# FRAM.net
KiCad netlist of a schematic drawn in Altium Designer
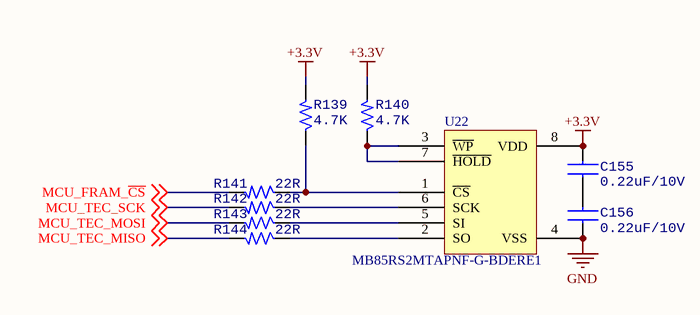
[diagram p0: FRAM.SchDoc]

(export (version "E")
  (design (tool "Eeschema 10.0.6"))
  (components
    (comp (ref "C155")
      (value "0.22uF/10V")
      (footprint "CAP-CER-0603")
      (libsource (lib "ID") (part "CAP-CER"))
    )
    (comp (ref "C156")
      (value "0.22uF/10V")
      (footprint "CAP-CER-0603")
      (libsource (lib "ID") (part "CAP-CER"))
    )
    (comp (ref "R139") (value "4.7K") (footprint "RES-SMD-0603") (libsource (lib "ID") (part "RES-SMD")))
    (comp (ref "R140") (value "4.7K") (footprint "RES-SMD-0603") (libsource (lib "ID") (part "RES-SMD")))
    (comp (ref "R141") (value "22R") (footprint "RES-SMD-0603") (libsource (lib "ID") (part "RES-SMD")))
    (comp (ref "R142") (value "22R") (footprint "RES-SMD-0603") (libsource (lib "ID") (part "RES-SMD")))
    (comp (ref "R143") (value "22R") (footprint "RES-SMD-0603") (libsource (lib "ID") (part "RES-SMD")))
    (comp (ref "R144") (value "22R") (footprint "RES-SMD-0603") (libsource (lib "ID") (part "RES-SMD")))
    (comp (ref "U22")
      (value "MB85RS2MTAPNF-G-BDERE1")
      (footprint "MB85RS2MTAPNF-G-BDERE1")
      (libsource (lib "LAB_B3_209_V1") (part "MB85RS2MTAPNF-G-BDERE1"))
    )
  )
  (nets
    (net (code "1") (name "+3.3V") (class "Default")
      (node (ref "C155") (pin "1") (pinfunction "1_1") (pintype "passive"))
      (node (ref "R139") (pin "2") (pinfunction "2_2") (pintype "passive"))
      (node (ref "R140") (pin "2") (pinfunction "2_2") (pintype "passive"))
      (node (ref "U22") (pin "8") (pinfunction "VDD_8") (pintype "passive"))
    )
    (net (code "2") (name "GND") (class "Default")
      (node (ref "C156") (pin "2") (pinfunction "2_2") (pintype "passive"))
      (node (ref "U22") (pin "4") (pinfunction "VSS_4") (pintype "passive"))
    )
    (net (code "3") (name "MCU_FRAM_~{CS}") (class "Default")
      (node (ref "R141") (pin "2") (pinfunction "2_2") (pintype "passive"))
    )
    (net (code "4") (name "MCU_TEC_MISO") (class "Default")
      (node (ref "R144") (pin "2") (pinfunction "2_2") (pintype "passive"))
    )
    (net (code "5") (name "MCU_TEC_MOSI") (class "Default")
      (node (ref "R143") (pin "2") (pinfunction "2_2") (pintype "passive"))
    )
    (net (code "6") (name "MCU_TEC_SCK") (class "Default")
      (node (ref "R142") (pin "2") (pinfunction "2_2") (pintype "passive"))
    )
    (net (code "7") (name "Net-(C155-Pad2)") (class "Default")
      (node (ref "C155") (pin "2") (pinfunction "2_2") (pintype "passive"))
      (node (ref "C156") (pin "1") (pinfunction "1_1") (pintype "passive"))
    )
    (net (code "8") (name "Net-(U22-SCK)") (class "Default")
      (node (ref "R142") (pin "1") (pinfunction "1_1") (pintype "passive"))
      (node (ref "U22") (pin "6") (pinfunction "SCK_6") (pintype "passive"))
    )
    (net (code "9") (name "Net-(U22-SI)") (class "Default")
      (node (ref "R143") (pin "1") (pinfunction "1_1") (pintype "passive"))
      (node (ref "U22") (pin "5") (pinfunction "SI_5") (pintype "passive"))
    )
    (net (code "10") (name "Net-(U22-SO)") (class "Default")
      (node (ref "R144") (pin "1") (pinfunction "1_1") (pintype "passive"))
      (node (ref "U22") (pin "2") (pinfunction "SO_2") (pintype "passive"))
    )
    (net (code "11") (name "Net-(U22-~{CS})") (class "Default")
      (node (ref "R139") (pin "1") (pinfunction "1_1") (pintype "passive"))
      (node (ref "R141") (pin "1") (pinfunction "1_1") (pintype "passive"))
      (node (ref "U22") (pin "1") (pinfunction "~{CS}_1") (pintype "passive"))
    )
    (net (code "12") (name "Net-(U22-~{HOLD})") (class "Default")
      (node (ref "R140") (pin "1") (pinfunction "1_1") (pintype "passive"))
      (node (ref "U22") (pin "3") (pinfunction "~{WP}_3") (pintype "passive"))
      (node (ref "U22") (pin "7") (pinfunction "~{HOLD}_7") (pintype "passive"))
    )
  )
)
